# Schaltung_WasserAnalyse_V1_2.net
KiCad netlist of a schematic drawn in EAGLE
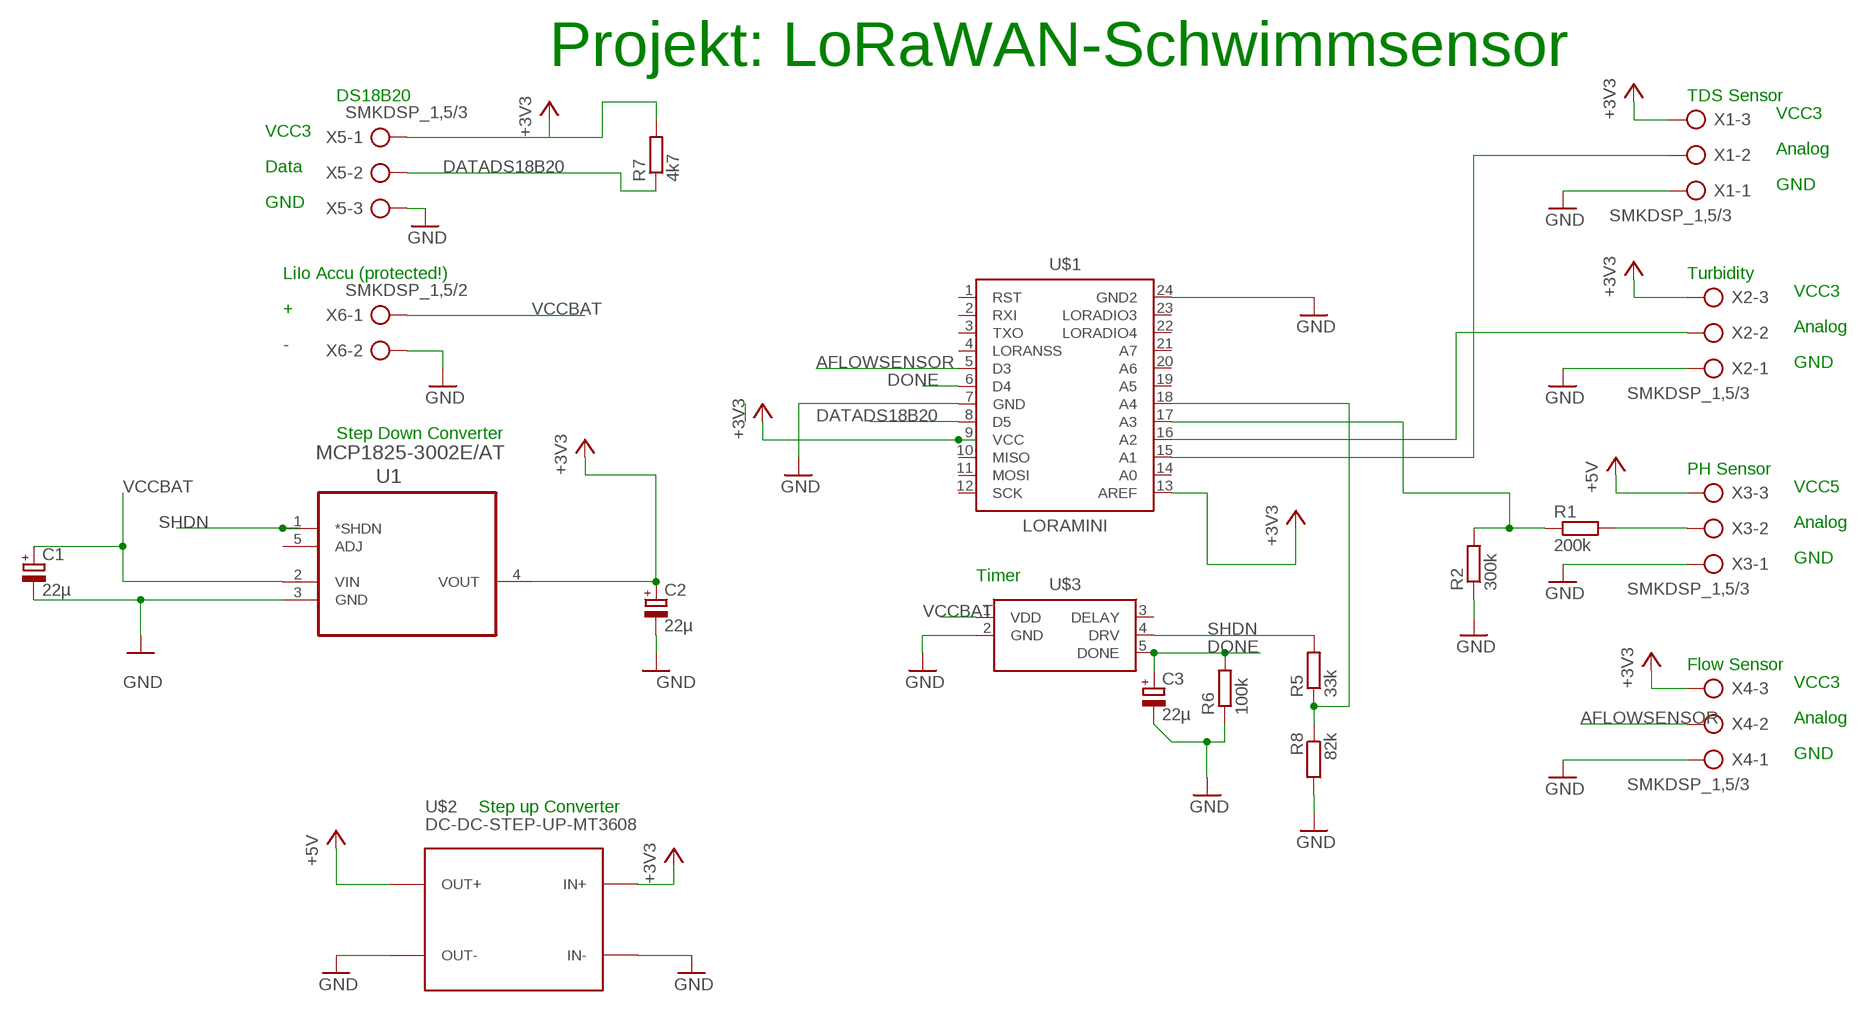
[diagram p0: schematic, sheet 1]

(export (version "E")
  (design (tool "Eeschema 10.0.6"))
  (components
    (comp (ref "C1")
      (value "22µ")
      (footprint "eagle-import:E2,5-5")
      (libsource (lib "eagle-import") (part "CPOL-EUE2.5-5"))
    )
    (comp (ref "C2")
      (value "22µ")
      (footprint "eagle-import:E2,5-5")
      (libsource (lib "eagle-import") (part "CPOL-EUE2.5-5"))
    )
    (comp (ref "C3")
      (value "22µ")
      (footprint "eagle-import:E2,5-5")
      (libsource (lib "eagle-import") (part "CPOL-EUE2.5-5"))
    )
    (comp (ref "R1")
      (value "200k")
      (footprint "eagle-import:0411_15")
      (libsource (lib "eagle-import") (part "R-EU_0411/15"))
    )
    (comp (ref "R2")
      (value "300k")
      (footprint "eagle-import:0411_15")
      (libsource (lib "eagle-import") (part "R-EU_0411/15"))
    )
    (comp (ref "R5")
      (value "33k")
      (footprint "eagle-import:0411_15")
      (libsource (lib "eagle-import") (part "R-EU_0411/15"))
    )
    (comp (ref "R6")
      (value "100k")
      (footprint "eagle-import:0411_15")
      (libsource (lib "eagle-import") (part "R-EU_0411/15"))
    )
    (comp (ref "R7")
      (value "4k7")
      (footprint "eagle-import:0411_15")
      (libsource (lib "eagle-import") (part "R-EU_0411/15"))
    )
    (comp (ref "R8")
      (value "82k")
      (footprint "eagle-import:0411_15")
      (libsource (lib "eagle-import") (part "R-EU_0411/15"))
    )
    (comp (ref "U$1")
      (value "LORAMINI")
      (footprint "eagle-import:LORAMINI")
      (libsource (lib "eagle-import") (part "LORAMINI"))
    )
    (comp (ref "U$2")
      (value "DC-DC-STEP-UP-MT3608")
      (footprint "eagle-import:DC-DC-STEP-UP-MT3608")
      (libsource (lib "eagle-import") (part "DC-DC-STEP-UP-MT3608"))
    )
    (comp (ref "U$3")
      (value "ADAFRUITTP5110")
      (footprint "eagle-import:MODULE")
      (libsource (lib "eagle-import") (part "ADAFRUITTP5110"))
    )
    (comp (ref "U1")
      (value "MCP1825-3002E/AT")
      (footprint "eagle-import:TO170P482X1024X3124-5P")
      (fields (field (name "DIGI-KEY_PART_NUMBER") "MCP1825-3002E/AT-ND") (field (name "MF") "Microchip"))
      (libsource (lib "eagle-import") (part "MCP1825-3002E/AT"))
    )
    (comp (ref "X1")
      (value "SMKDSP_1,5/3")
      (footprint "eagle-import:SMKDSP_1,5_3")
      (fields (field (name "MF") "FARNELL") (field (name "MPN") "1733583"))
      (libsource (lib "eagle-import") (part "SMKDSP_1,5/3"))
    )
    (comp (ref "X2")
      (value "SMKDSP_1,5/3")
      (footprint "eagle-import:SMKDSP_1,5_3")
      (fields (field (name "MF") "FARNELL") (field (name "MPN") "1733583"))
      (libsource (lib "eagle-import") (part "SMKDSP_1,5/3"))
    )
    (comp (ref "X3")
      (value "SMKDSP_1,5/3")
      (footprint "eagle-import:SMKDSP_1,5_3")
      (fields (field (name "MF") "FARNELL") (field (name "MPN") "1733583"))
      (libsource (lib "eagle-import") (part "SMKDSP_1,5/3"))
    )
    (comp (ref "X4")
      (value "SMKDSP_1,5/3")
      (footprint "eagle-import:SMKDSP_1,5_3")
      (fields (field (name "MF") "FARNELL") (field (name "MPN") "1733583"))
      (libsource (lib "eagle-import") (part "SMKDSP_1,5/3"))
    )
    (comp (ref "X5")
      (value "SMKDSP_1,5/3")
      (footprint "eagle-import:SMKDSP_1,5_3")
      (fields (field (name "MF") "FARNELL") (field (name "MPN") "1733583"))
      (libsource (lib "eagle-import") (part "SMKDSP_1,5/3"))
    )
    (comp (ref "X6")
      (value "SMKDSP_1,5/2")
      (footprint "eagle-import:SMKDSP_1,5_2")
      (fields (field (name "MF") "FARNELL") (field (name "MPN") "1733570"))
      (libsource (lib "eagle-import") (part "SMKDSP_1,5/2"))
    )
  )
  (nets
    (net (code "1") (name "+3V3") (class "Default")
      (node (ref "C2") (pin "+") (pinfunction "+_+") (pintype "passive"))
      (node (ref "R7") (pin "2") (pinfunction "2_2") (pintype "passive"))
      (node (ref "U$1") (pin "13") (pinfunction "AREF_13") (pintype "bidirectional"))
      (node (ref "U$1") (pin "9") (pinfunction "VCC_9") (pintype "bidirectional"))
      (node (ref "U$2") (pin "IN+") (pinfunction "IN+_IN+") (pintype "bidirectional"))
      (node (ref "U1") (pin "4") (pinfunction "VOUT_4") (pintype "output"))
      (node (ref "X1") (pin "3") (pinfunction "KL_3") (pintype "passive"))
      (node (ref "X2") (pin "3") (pinfunction "KL_3") (pintype "passive"))
      (node (ref "X4") (pin "3") (pinfunction "KL_3") (pintype "passive"))
      (node (ref "X5") (pin "1") (pinfunction "KL_1") (pintype "passive"))
    )
    (net (code "2") (name "+5V") (class "Default")
      (node (ref "U$2") (pin "OUT+") (pinfunction "OUT+_OUT+") (pintype "bidirectional"))
      (node (ref "X3") (pin "3") (pinfunction "KL_3") (pintype "passive"))
    )
    (net (code "3") (name "/AFLOWSENSOR") (class "Default")
      (node (ref "U$1") (pin "5") (pinfunction "D3_5") (pintype "bidirectional"))
      (node (ref "X4") (pin "2") (pinfunction "KL_2") (pintype "passive"))
    )
    (net (code "4") (name "/DATADS18B20") (class "Default")
      (node (ref "R7") (pin "1") (pinfunction "1_1") (pintype "passive"))
      (node (ref "U$1") (pin "8") (pinfunction "D5_8") (pintype "bidirectional"))
      (node (ref "X5") (pin "2") (pinfunction "KL_2") (pintype "passive"))
    )
    (net (code "5") (name "/DONE") (class "Default")
      (node (ref "C3") (pin "+") (pinfunction "+_+") (pintype "passive"))
      (node (ref "R6") (pin "2") (pinfunction "2_2") (pintype "passive"))
      (node (ref "U$1") (pin "6") (pinfunction "D4_6") (pintype "bidirectional"))
      (node (ref "U$3") (pin "5") (pinfunction "DONE_5") (pintype "bidirectional"))
    )
    (net (code "6") (name "/SHDN") (class "Default")
      (node (ref "R5") (pin "2") (pinfunction "2_2") (pintype "passive"))
      (node (ref "U$3") (pin "4") (pinfunction "DRV_4") (pintype "bidirectional"))
      (node (ref "U1") (pin "1") (pinfunction "*SHDN_1") (pintype "input"))
    )
    (net (code "7") (name "/VCCBAT") (class "Default")
      (node (ref "C1") (pin "+") (pinfunction "+_+") (pintype "passive"))
      (node (ref "U$3") (pin "1") (pinfunction "VDD_1") (pintype "bidirectional"))
      (node (ref "U1") (pin "2") (pinfunction "VIN_2") (pintype "input"))
      (node (ref "X6") (pin "1") (pinfunction "KL_1") (pintype "passive"))
    )
    (net (code "8") (name "GND") (class "Default")
      (node (ref "C1") (pin "-") (pinfunction "-_-") (pintype "passive"))
      (node (ref "C2") (pin "-") (pinfunction "-_-") (pintype "passive"))
      (node (ref "C3") (pin "-") (pinfunction "-_-") (pintype "passive"))
      (node (ref "R2") (pin "1") (pinfunction "1_1") (pintype "passive"))
      (node (ref "R6") (pin "1") (pinfunction "1_1") (pintype "passive"))
      (node (ref "R8") (pin "2") (pinfunction "2_2") (pintype "passive"))
      (node (ref "U$1") (pin "24") (pinfunction "GND2_24") (pintype "bidirectional"))
      (node (ref "U$1") (pin "7") (pinfunction "GND_7") (pintype "bidirectional"))
      (node (ref "U$2") (pin "IN-") (pinfunction "IN-_IN-") (pintype "bidirectional"))
      (node (ref "U$2") (pin "OUT-") (pinfunction "OUT-_OUT-") (pintype "bidirectional"))
      (node (ref "U$3") (pin "2") (pinfunction "GND_2") (pintype "bidirectional"))
      (node (ref "U1") (pin "3") (pinfunction "GND_3") (pintype "passive"))
      (node (ref "X1") (pin "1") (pinfunction "KL_1") (pintype "passive"))
      (node (ref "X2") (pin "1") (pinfunction "KL_1") (pintype "passive"))
      (node (ref "X3") (pin "1") (pinfunction "KL_1") (pintype "passive"))
      (node (ref "X4") (pin "1") (pinfunction "KL_1") (pintype "passive"))
      (node (ref "X5") (pin "3") (pinfunction "KL_3") (pintype "passive"))
      (node (ref "X6") (pin "2") (pinfunction "KL_2") (pintype "passive"))
    )
    (net (code "9") (name "Net-(U$1-A1)") (class "Default")
      (node (ref "U$1") (pin "15") (pinfunction "A1_15") (pintype "bidirectional"))
      (node (ref "X1") (pin "2") (pinfunction "KL_2") (pintype "passive"))
    )
    (net (code "10") (name "Net-(U$1-A2)") (class "Default")
      (node (ref "U$1") (pin "16") (pinfunction "A2_16") (pintype "bidirectional"))
      (node (ref "X2") (pin "2") (pinfunction "KL_2") (pintype "passive"))
    )
    (net (code "11") (name "Net-(U$1-A3)") (class "Default")
      (node (ref "R1") (pin "1") (pinfunction "1_1") (pintype "passive"))
      (node (ref "R2") (pin "2") (pinfunction "2_2") (pintype "passive"))
      (node (ref "U$1") (pin "17") (pinfunction "A3_17") (pintype "bidirectional"))
    )
    (net (code "12") (name "Net-(U$1-A4)") (class "Default")
      (node (ref "R5") (pin "1") (pinfunction "1_1") (pintype "passive"))
      (node (ref "R8") (pin "1") (pinfunction "1_1") (pintype "passive"))
      (node (ref "U$1") (pin "18") (pinfunction "A4_18") (pintype "bidirectional"))
    )
    (net (code "13") (name "Net-(X3B-KL)") (class "Default")
      (node (ref "R1") (pin "2") (pinfunction "2_2") (pintype "passive"))
      (node (ref "X3") (pin "2") (pinfunction "KL_2") (pintype "passive"))
    )
    (net (code "14") (name "unconnected-(U$1-A0-Pad14)") (class "Default")
      (node (ref "U$1") (pin "14") (pinfunction "A0_14") (pintype "bidirectional"))
    )
    (net (code "15") (name "unconnected-(U$1-A5-Pad19)") (class "Default")
      (node (ref "U$1") (pin "19") (pinfunction "A5_19") (pintype "bidirectional"))
    )
    (net (code "16") (name "unconnected-(U$1-A6-Pad20)") (class "Default")
      (node (ref "U$1") (pin "20") (pinfunction "A6_20") (pintype "bidirectional"))
    )
    (net (code "17") (name "unconnected-(U$1-A7-Pad21)") (class "Default")
      (node (ref "U$1") (pin "21") (pinfunction "A7_21") (pintype "bidirectional"))
    )
    (net (code "18") (name "unconnected-(U$1-LORADIO3-Pad23)") (class "Default")
      (node (ref "U$1") (pin "23") (pinfunction "LORADIO3_23") (pintype "bidirectional"))
    )
    (net (code "19") (name "unconnected-(U$1-LORADIO4-Pad22)") (class "Default")
      (node (ref "U$1") (pin "22") (pinfunction "LORADIO4_22") (pintype "bidirectional"))
    )
    (net (code "20") (name "unconnected-(U$1-LORANSS-Pad4)") (class "Default")
      (node (ref "U$1") (pin "4") (pinfunction "LORANSS_4") (pintype "bidirectional"))
    )
    (net (code "21") (name "unconnected-(U$1-MISO-Pad10)") (class "Default")
      (node (ref "U$1") (pin "10") (pinfunction "MISO_10") (pintype "bidirectional"))
    )
    (net (code "22") (name "unconnected-(U$1-MOSI-Pad11)") (class "Default")
      (node (ref "U$1") (pin "11") (pinfunction "MOSI_11") (pintype "bidirectional"))
    )
    (net (code "23") (name "unconnected-(U$1-RST-Pad1)") (class "Default")
      (node (ref "U$1") (pin "1") (pinfunction "RST_1") (pintype "input"))
    )
    (net (code "24") (name "unconnected-(U$1-RXI-Pad2)") (class "Default")
      (node (ref "U$1") (pin "2") (pinfunction "RXI_2") (pintype "input"))
    )
    (net (code "25") (name "unconnected-(U$1-SCK-Pad12)") (class "Default")
      (node (ref "U$1") (pin "12") (pinfunction "SCK_12") (pintype "bidirectional"))
    )
    (net (code "26") (name "unconnected-(U$1-TXO-Pad3)") (class "Default")
      (node (ref "U$1") (pin "3") (pinfunction "TXO_3") (pintype "output"))
    )
    (net (code "27") (name "unconnected-(U$3-DELAY-Pad3)") (class "Default")
      (node (ref "U$3") (pin "3") (pinfunction "DELAY_3") (pintype "bidirectional"))
    )
    (net (code "28") (name "unconnected-(U1-ADJ-Pad5)") (class "Default")
      (node (ref "U1") (pin "5") (pinfunction "ADJ_5") (pintype "output"))
    )
  )
)
